# voltage_conditioning.net
KiCad netlist of a schematic drawn in Altium Designer
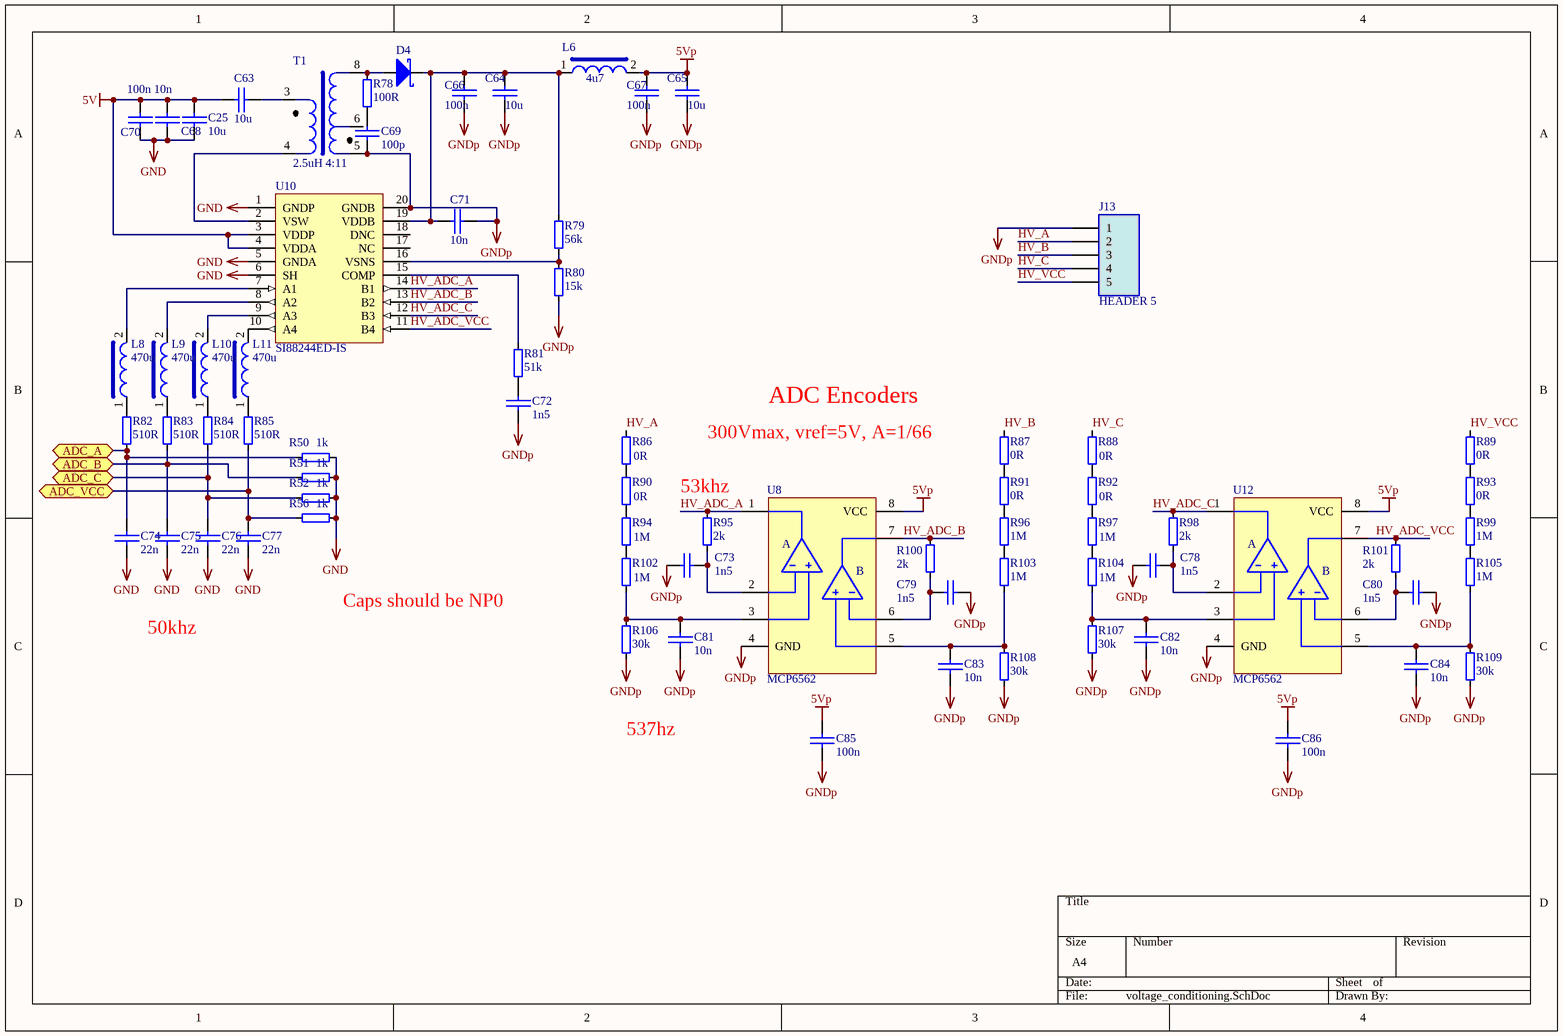
[diagram p0: voltage_conditioning.SchDoc]

(export (version "E")
  (design (tool "Eeschema 10.0.6"))
  (components
    (comp (ref "C25")
      (value "10u")
      (footprint "0805")
      (description "Capacitor")
      (libsource (lib "Schematic Library") (part "CAPACITOR"))
    )
    (comp (ref "C63")
      (value "10u")
      (footprint "0805")
      (description "Capacitor")
      (libsource (lib "Schematic Library") (part "CAPACITOR"))
    )
    (comp (ref "C64")
      (value "10u")
      (footprint "0805")
      (description "Capacitor")
      (libsource (lib "Schematic Library") (part "CAPACITOR"))
    )
    (comp (ref "C65")
      (value "10u")
      (footprint "0805")
      (description "Capacitor")
      (libsource (lib "Schematic Library") (part "CAPACITOR"))
    )
    (comp (ref "C66")
      (value "100n")
      (footprint "0603")
      (description "Capacitor")
      (libsource (lib "Schematic Library") (part "CAPACITOR"))
    )
    (comp (ref "C67")
      (value "100n")
      (footprint "0603")
      (description "Capacitor")
      (libsource (lib "Schematic Library") (part "CAPACITOR"))
    )
    (comp (ref "C68")
      (value "10n")
      (footprint "0603")
      (description "Capacitor")
      (libsource (lib "Schematic Library") (part "CAPACITOR"))
    )
    (comp (ref "C69")
      (value "100p")
      (footprint "0603")
      (fields (field (name "DIGIKEY PART NUMBER") "PCC2153CT-ND"))
      (libsource (lib "*") (part "CAP"))
    )
    (comp (ref "C70")
      (value "100n")
      (footprint "0603")
      (description "Capacitor")
      (libsource (lib "Schematic Library") (part "CAPACITOR"))
    )
    (comp (ref "C71")
      (value "10n")
      (footprint "0603")
      (description "Capacitor")
      (libsource (lib "Schematic Library") (part "CAPACITOR"))
    )
    (comp (ref "C72")
      (value "1n5")
      (footprint "0603")
      (fields (field (name "DIGIKEY PART NUMBER") "PCC2153CT-ND"))
      (libsource (lib "*") (part "CAP"))
    )
    (comp (ref "C73")
      (value "1n5")
      (footprint "0603")
      (description "COG/NPO")
      (libsource (lib "Schematic Library") (part "CAPACITOR"))
    )
    (comp (ref "C74")
      (value "22n")
      (footprint "0603")
      (description "Capacitor")
      (libsource (lib "Schematic Library") (part "CAPACITOR"))
    )
    (comp (ref "C75")
      (value "22n")
      (footprint "0603")
      (description "Capacitor")
      (libsource (lib "Schematic Library") (part "CAPACITOR"))
    )
    (comp (ref "C76")
      (value "22n")
      (footprint "0603")
      (description "Capacitor")
      (libsource (lib "Schematic Library") (part "CAPACITOR"))
    )
    (comp (ref "C77")
      (value "22n")
      (footprint "0603")
      (description "Capacitor")
      (libsource (lib "Schematic Library") (part "CAPACITOR"))
    )
    (comp (ref "C78")
      (value "1n5")
      (footprint "0603")
      (description "COG/NPO")
      (libsource (lib "Schematic Library") (part "CAPACITOR"))
    )
    (comp (ref "C79")
      (value "1n5")
      (footprint "0603")
      (description "Capacitor")
      (libsource (lib "Schematic Library") (part "CAPACITOR"))
    )
    (comp (ref "C80")
      (value "1n5")
      (footprint "0603")
      (description "Capacitor")
      (libsource (lib "Schematic Library") (part "CAPACITOR"))
    )
    (comp (ref "C81")
      (value "10n")
      (footprint "0603")
      (description "Capacitor")
      (libsource (lib "Schematic Library") (part "CAPACITOR"))
    )
    (comp (ref "C82")
      (value "10n")
      (footprint "0603")
      (description "Capacitor")
      (libsource (lib "Schematic Library") (part "CAPACITOR"))
    )
    (comp (ref "C83")
      (value "10n")
      (footprint "0603")
      (description "Capacitor")
      (libsource (lib "Schematic Library") (part "CAPACITOR"))
    )
    (comp (ref "C84")
      (value "10n")
      (footprint "0603")
      (description "Capacitor")
      (libsource (lib "Schematic Library") (part "CAPACITOR"))
    )
    (comp (ref "C85") (value "100n") (footprint "0603") (libsource (lib "*") (part "CAP")))
    (comp (ref "C86") (value "100n") (footprint "0603") (libsource (lib "*") (part "CAP")))
    (comp (ref "D4")
      (value "DIODE SCHOTTKY")
      (footprint "SOD323-AK")
      (description "Schottky Diode")
      (libsource (lib "Schematic Library") (part "DIODE SCHOTTKY"))
    )
    (comp (ref "J13")
      (value "HEADER 5")
      (footprint "HDR5-5mm")
      (description "4 Pin Header")
      (libsource (lib "Schematic Library") (part "HEADER 5"))
    )
    (comp (ref "L6")
      (value "4u7")
      (footprint "0805")
      (description "Standard single coil inductor")
      (fields (field (name "DIGIKEY PART NUMBER") "587-2907-1-ND"))
      (libsource (lib "Schematic Library") (part "INDUCTOR-1 COIL"))
    )
    (comp (ref "L8")
      (value "470u")
      (footprint "0805")
      (description "Standard single coil inductor")
      (libsource (lib "Schematic Library") (part "INDUCTOR-1 COIL"))
    )
    (comp (ref "L9")
      (value "470u")
      (footprint "0805")
      (description "Standard single coil inductor")
      (libsource (lib "Schematic Library") (part "INDUCTOR-1 COIL"))
    )
    (comp (ref "L10")
      (value "470u")
      (footprint "0805")
      (description "Standard single coil inductor")
      (libsource (lib "Schematic Library") (part "INDUCTOR-1 COIL"))
    )
    (comp (ref "L11")
      (value "470u")
      (footprint "0805")
      (description "Standard single coil inductor")
      (libsource (lib "Schematic Library") (part "INDUCTOR-1 COIL"))
    )
    (comp (ref "R50")
      (value "1k")
      (footprint "0603")
      (description "Resistor")
      (libsource (lib "Schematic Library") (part "RESISTOR"))
    )
    (comp (ref "R51")
      (value "1k")
      (footprint "0603")
      (description "Resistor")
      (libsource (lib "Schematic Library") (part "RESISTOR"))
    )
    (comp (ref "R52")
      (value "1k")
      (footprint "0603")
      (description "Resistor")
      (libsource (lib "Schematic Library") (part "RESISTOR"))
    )
    (comp (ref "R56")
      (value "1k")
      (footprint "0603")
      (description "Resistor")
      (libsource (lib "Schematic Library") (part "RESISTOR"))
    )
    (comp (ref "R78")
      (value "100R")
      (footprint "0603")
      (description "Resistor")
      (libsource (lib "Schematic Library") (part "RESISTOR"))
    )
    (comp (ref "R79")
      (value "56k")
      (footprint "0603")
      (description "Resistor")
      (libsource (lib "Schematic Library") (part "RESISTOR"))
    )
    (comp (ref "R80")
      (value "15k")
      (footprint "0603")
      (description "Resistor")
      (libsource (lib "Schematic Library") (part "RESISTOR"))
    )
    (comp (ref "R81")
      (value "51k")
      (footprint "0603")
      (description "Resistor")
      (libsource (lib "Schematic Library") (part "RESISTOR"))
    )
    (comp (ref "R82")
      (value "510R")
      (footprint "0603")
      (description "Resistor")
      (libsource (lib "Schematic Library") (part "RESISTOR"))
    )
    (comp (ref "R83")
      (value "510R")
      (footprint "0603")
      (description "Resistor")
      (libsource (lib "Schematic Library") (part "RESISTOR"))
    )
    (comp (ref "R84")
      (value "510R")
      (footprint "0603")
      (description "Resistor")
      (libsource (lib "Schematic Library") (part "RESISTOR"))
    )
    (comp (ref "R85")
      (value "510R")
      (footprint "0603")
      (description "Resistor")
      (libsource (lib "Schematic Library") (part "RESISTOR"))
    )
    (comp (ref "R86")
      (value "0R")
      (footprint "1206")
      (description "Resistor")
      (libsource (lib "Schematic Library") (part "RESISTOR"))
    )
    (comp (ref "R87")
      (value "0R")
      (footprint "1206")
      (description "Resistor")
      (libsource (lib "Schematic Library") (part "RESISTOR"))
    )
    (comp (ref "R88")
      (value "0R")
      (footprint "1206")
      (description "Resistor")
      (libsource (lib "Schematic Library") (part "RESISTOR"))
    )
    (comp (ref "R89")
      (value "0R")
      (footprint "1206")
      (description "Resistor")
      (libsource (lib "Schematic Library") (part "RESISTOR"))
    )
    (comp (ref "R90")
      (value "0R")
      (footprint "1206")
      (description "Resistor")
      (libsource (lib "Schematic Library") (part "RESISTOR"))
    )
    (comp (ref "R91")
      (value "0R")
      (footprint "1206")
      (description "Resistor")
      (libsource (lib "Schematic Library") (part "RESISTOR"))
    )
    (comp (ref "R92")
      (value "0R")
      (footprint "1206")
      (description "Resistor")
      (libsource (lib "Schematic Library") (part "RESISTOR"))
    )
    (comp (ref "R93")
      (value "0R")
      (footprint "1206")
      (description "Resistor")
      (libsource (lib "Schematic Library") (part "RESISTOR"))
    )
    (comp (ref "R94")
      (value "1M")
      (footprint "1206")
      (description "Resistor")
      (libsource (lib "Schematic Library") (part "RESISTOR"))
    )
    (comp (ref "R95")
      (value "2k")
      (footprint "0603")
      (description "Resistor")
      (libsource (lib "Schematic Library") (part "RESISTOR"))
    )
    (comp (ref "R96")
      (value "1M")
      (footprint "1206")
      (description "Resistor")
      (libsource (lib "Schematic Library") (part "RESISTOR"))
    )
    (comp (ref "R97")
      (value "1M")
      (footprint "1206")
      (description "Resistor")
      (libsource (lib "Schematic Library") (part "RESISTOR"))
    )
    (comp (ref "R98")
      (value "2k")
      (footprint "0603")
      (description "Resistor")
      (libsource (lib "Schematic Library") (part "RESISTOR"))
    )
    (comp (ref "R99")
      (value "1M")
      (footprint "1206")
      (description "Resistor")
      (libsource (lib "Schematic Library") (part "RESISTOR"))
    )
    (comp (ref "R100")
      (value "2k")
      (footprint "0603")
      (description "Resistor")
      (libsource (lib "Schematic Library") (part "RESISTOR"))
    )
    (comp (ref "R101")
      (value "2k")
      (footprint "0603")
      (description "Resistor")
      (libsource (lib "Schematic Library") (part "RESISTOR"))
    )
    (comp (ref "R102")
      (value "1M")
      (footprint "1206")
      (description "Resistor")
      (libsource (lib "Schematic Library") (part "RESISTOR"))
    )
    (comp (ref "R103")
      (value "1M")
      (footprint "1206")
      (description "Resistor")
      (libsource (lib "Schematic Library") (part "RESISTOR"))
    )
    (comp (ref "R104")
      (value "1M")
      (footprint "1206")
      (description "Resistor")
      (libsource (lib "Schematic Library") (part "RESISTOR"))
    )
    (comp (ref "R105")
      (value "1M")
      (footprint "1206")
      (description "Resistor")
      (libsource (lib "Schematic Library") (part "RESISTOR"))
    )
    (comp (ref "R106")
      (value "30k")
      (footprint "0603")
      (description "Resistor")
      (libsource (lib "Schematic Library") (part "RESISTOR"))
    )
    (comp (ref "R107")
      (value "30k")
      (footprint "0603")
      (description "Resistor")
      (libsource (lib "Schematic Library") (part "RESISTOR"))
    )
    (comp (ref "R108")
      (value "30k")
      (footprint "0603")
      (description "Resistor")
      (libsource (lib "Schematic Library") (part "RESISTOR"))
    )
    (comp (ref "R109")
      (value "30k")
      (footprint "0603")
      (description "Resistor")
      (libsource (lib "Schematic Library") (part "RESISTOR"))
    )
    (comp (ref "T1")
      (value "2.5uH 4:11")
      (footprint "RM5/I")
      (description "2Coil Transformer 1 on left 1 on right with tap")
      (libsource (lib "LBC") (part "TRANSFORMER-2 COIL 1L 1R_1t"))
    )
    (comp (ref "U8")
      (value "MCP6562")
      (footprint "MSOP8")
      (libsource (lib "Schematic Library") (part "COMPARATOR DUAL draft"))
    )
    (comp (ref "U10")
      (value "SI88244ED-IS")
      (footprint "SLAB-SOIC-20-WB_N")
      (fields (field (name "MANUFACTURER") "Silicon Labs") (field (name "PARTNUMBER") "SI88243ED-IS"))
      (libsource (lib "LBC") (part "SI88243ED-IS"))
    )
    (comp (ref "U12")
      (value "MCP6562")
      (footprint "MSOP8")
      (libsource (lib "Schematic Library") (part "COMPARATOR DUAL draft"))
    )
  )
  (nets
    (net (code "1") (name "/ADC_A") (class "Default")
      (node (ref "C74") (pin "2") (pinfunction "2_2") (pintype "passive"))
      (node (ref "R50") (pin "2") (pintype "passive"))
      (node (ref "R82") (pin "1") (pintype "passive"))
    )
    (net (code "2") (name "/ADC_B") (class "Default")
      (node (ref "C75") (pin "2") (pinfunction "2_2") (pintype "passive"))
      (node (ref "R51") (pin "2") (pintype "passive"))
      (node (ref "R83") (pin "1") (pintype "passive"))
    )
    (net (code "3") (name "/ADC_C") (class "Default")
      (node (ref "C76") (pin "2") (pinfunction "2_2") (pintype "passive"))
      (node (ref "R52") (pin "2") (pintype "passive"))
      (node (ref "R84") (pin "1") (pintype "passive"))
    )
    (net (code "4") (name "/ADC_VCC") (class "Default")
      (node (ref "C77") (pin "2") (pinfunction "2_2") (pintype "passive"))
      (node (ref "R56") (pin "2") (pintype "passive"))
      (node (ref "R85") (pin "1") (pintype "passive"))
    )
    (net (code "5") (name "/HV_A") (class "Default")
      (node (ref "J13") (pin "2") (pinfunction "2_2") (pintype "passive"))
      (node (ref "R86") (pin "2") (pintype "passive"))
    )
    (net (code "6") (name "/HV_ADC_A") (class "Default")
      (node (ref "R95") (pin "2") (pintype "passive"))
      (node (ref "U10") (pin "14") (pinfunction "B1_14") (pintype "output"))
      (node (ref "U8") (pin "1") (pinfunction "OUTA_1") (pintype "passive"))
    )
    (net (code "7") (name "/HV_ADC_B") (class "Default")
      (node (ref "R100") (pin "2") (pintype "passive"))
      (node (ref "U10") (pin "13") (pinfunction "B2_13") (pintype "input"))
      (node (ref "U8") (pin "7") (pinfunction "OUTB_7") (pintype "passive"))
    )
    (net (code "8") (name "/HV_ADC_C") (class "Default")
      (node (ref "R98") (pin "2") (pintype "passive"))
      (node (ref "U10") (pin "12") (pinfunction "B3_12") (pintype "input"))
      (node (ref "U12") (pin "1") (pinfunction "OUTA_1") (pintype "passive"))
    )
    (net (code "9") (name "/HV_ADC_VCC") (class "Default")
      (node (ref "R101") (pin "2") (pintype "passive"))
      (node (ref "U10") (pin "11") (pinfunction "B4_11") (pintype "input"))
      (node (ref "U12") (pin "7") (pinfunction "OUTB_7") (pintype "passive"))
    )
    (net (code "10") (name "/HV_B") (class "Default")
      (node (ref "J13") (pin "3") (pinfunction "3_3") (pintype "passive"))
      (node (ref "R87") (pin "2") (pintype "passive"))
    )
    (net (code "11") (name "/HV_C") (class "Default")
      (node (ref "J13") (pin "4") (pinfunction "4_4") (pintype "passive"))
      (node (ref "R88") (pin "2") (pintype "passive"))
    )
    (net (code "12") (name "/HV_VCC") (class "Default")
      (node (ref "J13") (pin "5") (pinfunction "5_5") (pintype "passive"))
      (node (ref "R89") (pin "2") (pintype "passive"))
    )
    (net (code "13") (name "5V") (class "Default")
      (node (ref "C25") (pin "2") (pinfunction "2_2") (pintype "passive"))
      (node (ref "C63") (pin "1") (pinfunction "1_1") (pintype "passive"))
      (node (ref "C68") (pin "1") (pinfunction "1_1") (pintype "passive"))
      (node (ref "C70") (pin "1") (pinfunction "1_1") (pintype "passive"))
      (node (ref "U10") (pin "3") (pinfunction "VDDP_3") (pintype "passive"))
      (node (ref "U10") (pin "4") (pinfunction "VDDA_4") (pintype "passive"))
    )
    (net (code "14") (name "5Vp") (class "Default")
      (node (ref "C65") (pin "1") (pinfunction "1_1") (pintype "passive"))
      (node (ref "C67") (pin "1") (pinfunction "1_1") (pintype "passive"))
      (node (ref "C85") (pin "1") (pinfunction "1_1") (pintype "passive"))
      (node (ref "C86") (pin "1") (pinfunction "1_1") (pintype "passive"))
      (node (ref "L6") (pin "2") (pinfunction "2_2") (pintype "passive"))
      (node (ref "U12") (pin "8") (pinfunction "VCC_8") (pintype "passive"))
      (node (ref "U8") (pin "8") (pinfunction "VCC_8") (pintype "passive"))
    )
    (net (code "15") (name "GND") (class "Default")
      (node (ref "C25") (pin "1") (pinfunction "1_1") (pintype "passive"))
      (node (ref "C68") (pin "2") (pinfunction "2_2") (pintype "passive"))
      (node (ref "C70") (pin "2") (pinfunction "2_2") (pintype "passive"))
      (node (ref "C74") (pin "1") (pinfunction "1_1") (pintype "passive"))
      (node (ref "C75") (pin "1") (pinfunction "1_1") (pintype "passive"))
      (node (ref "C76") (pin "1") (pinfunction "1_1") (pintype "passive"))
      (node (ref "C77") (pin "1") (pinfunction "1_1") (pintype "passive"))
      (node (ref "R50") (pin "1") (pintype "passive"))
      (node (ref "R51") (pin "1") (pintype "passive"))
      (node (ref "R52") (pin "1") (pintype "passive"))
      (node (ref "R56") (pin "1") (pintype "passive"))
      (node (ref "U10") (pin "1") (pinfunction "GNDP_1") (pintype "passive"))
      (node (ref "U10") (pin "5") (pinfunction "GNDA_5") (pintype "passive"))
      (node (ref "U10") (pin "6") (pinfunction "SH_6") (pintype "passive"))
    )
    (net (code "16") (name "GNDp") (class "Default")
      (node (ref "C64") (pin "2") (pinfunction "2_2") (pintype "passive"))
      (node (ref "C65") (pin "2") (pinfunction "2_2") (pintype "passive"))
      (node (ref "C66") (pin "2") (pinfunction "2_2") (pintype "passive"))
      (node (ref "C67") (pin "2") (pinfunction "2_2") (pintype "passive"))
      (node (ref "C69") (pin "2") (pinfunction "2_2") (pintype "passive"))
      (node (ref "C71") (pin "2") (pinfunction "2_2") (pintype "passive"))
      (node (ref "C72") (pin "2") (pinfunction "2_2") (pintype "passive"))
      (node (ref "C73") (pin "1") (pinfunction "1_1") (pintype "passive"))
      (node (ref "C78") (pin "1") (pinfunction "1_1") (pintype "passive"))
      (node (ref "C79") (pin "1") (pinfunction "1_1") (pintype "passive"))
      (node (ref "C80") (pin "1") (pinfunction "1_1") (pintype "passive"))
      (node (ref "C81") (pin "1") (pinfunction "1_1") (pintype "passive"))
      (node (ref "C82") (pin "1") (pinfunction "1_1") (pintype "passive"))
      (node (ref "C83") (pin "2") (pinfunction "2_2") (pintype "passive"))
      (node (ref "C84") (pin "2") (pinfunction "2_2") (pintype "passive"))
      (node (ref "C85") (pin "2") (pinfunction "2_2") (pintype "passive"))
      (node (ref "C86") (pin "2") (pinfunction "2_2") (pintype "passive"))
      (node (ref "J13") (pin "1") (pinfunction "1_1") (pintype "passive"))
      (node (ref "R106") (pin "1") (pintype "passive"))
      (node (ref "R107") (pin "1") (pintype "passive"))
      (node (ref "R108") (pin "2") (pintype "passive"))
      (node (ref "R109") (pin "2") (pintype "passive"))
      (node (ref "R80") (pin "2") (pintype "passive"))
      (node (ref "T1") (pin "5") (pinfunction "5_5") (pintype "passive"))
      (node (ref "U10") (pin "20") (pinfunction "GNDB_20") (pintype "passive"))
      (node (ref "U12") (pin "4") (pinfunction "GND_4") (pintype "passive"))
      (node (ref "U8") (pin "4") (pinfunction "GND_4") (pintype "passive"))
    )
    (net (code "17") (name "Net-(C63-Pad2)") (class "Default")
      (node (ref "C63") (pin "2") (pinfunction "2_2") (pintype "passive"))
      (node (ref "T1") (pin "3") (pinfunction "3_3") (pintype "passive"))
    )
    (net (code "18") (name "Net-(C69-Pad1)") (class "Default")
      (node (ref "C69") (pin "1") (pinfunction "1_1") (pintype "passive"))
      (node (ref "R78") (pin "1") (pintype "passive"))
    )
    (net (code "19") (name "Net-(C72-Pad1)") (class "Default")
      (node (ref "C72") (pin "1") (pinfunction "1_1") (pintype "passive"))
      (node (ref "R81") (pin "1") (pintype "passive"))
    )
    (net (code "20") (name "Net-(D4-PadA)") (class "Default")
      (node (ref "D4") (pin "A") (pinfunction "A_A") (pintype "passive"))
      (node (ref "R78") (pin "2") (pintype "passive"))
      (node (ref "T1") (pin "8") (pinfunction "8_8") (pintype "passive"))
    )
    (net (code "21") (name "Net-(L8-Pad1)") (class "Default")
      (node (ref "L8") (pin "1") (pinfunction "1_1") (pintype "passive"))
      (node (ref "R82") (pin "2") (pintype "passive"))
    )
    (net (code "22") (name "Net-(L9-Pad1)") (class "Default")
      (node (ref "L9") (pin "1") (pinfunction "1_1") (pintype "passive"))
      (node (ref "R83") (pin "2") (pintype "passive"))
    )
    (net (code "23") (name "Net-(L10-Pad1)") (class "Default")
      (node (ref "L10") (pin "1") (pinfunction "1_1") (pintype "passive"))
      (node (ref "R84") (pin "2") (pintype "passive"))
    )
    (net (code "24") (name "Net-(L11-Pad1)") (class "Default")
      (node (ref "L11") (pin "1") (pinfunction "1_1") (pintype "passive"))
      (node (ref "R85") (pin "2") (pintype "passive"))
    )
    (net (code "25") (name "Net-(R86-Pad1)") (class "Default")
      (node (ref "R86") (pin "1") (pintype "passive"))
      (node (ref "R90") (pin "2") (pintype "passive"))
    )
    (net (code "26") (name "Net-(R87-Pad1)") (class "Default")
      (node (ref "R87") (pin "1") (pintype "passive"))
      (node (ref "R91") (pin "2") (pintype "passive"))
    )
    (net (code "27") (name "Net-(R88-Pad1)") (class "Default")
      (node (ref "R88") (pin "1") (pintype "passive"))
      (node (ref "R92") (pin "2") (pintype "passive"))
    )
    (net (code "28") (name "Net-(R89-Pad1)") (class "Default")
      (node (ref "R89") (pin "1") (pintype "passive"))
      (node (ref "R93") (pin "2") (pintype "passive"))
    )
    (net (code "29") (name "Net-(R90-Pad1)") (class "Default")
      (node (ref "R90") (pin "1") (pintype "passive"))
      (node (ref "R94") (pin "2") (pintype "passive"))
    )
    (net (code "30") (name "Net-(R91-Pad1)") (class "Default")
      (node (ref "R91") (pin "1") (pintype "passive"))
      (node (ref "R96") (pin "2") (pintype "passive"))
    )
    (net (code "31") (name "Net-(R92-Pad1)") (class "Default")
      (node (ref "R92") (pin "1") (pintype "passive"))
      (node (ref "R97") (pin "2") (pintype "passive"))
    )
    (net (code "32") (name "Net-(R93-Pad1)") (class "Default")
      (node (ref "R93") (pin "1") (pintype "passive"))
      (node (ref "R99") (pin "2") (pintype "passive"))
    )
    (net (code "33") (name "Net-(R102-Pad2)") (class "Default")
      (node (ref "R102") (pin "2") (pintype "passive"))
      (node (ref "R94") (pin "1") (pintype "passive"))
    )
    (net (code "34") (name "Net-(R103-Pad2)") (class "Default")
      (node (ref "R103") (pin "2") (pintype "passive"))
      (node (ref "R96") (pin "1") (pintype "passive"))
    )
    (net (code "35") (name "Net-(R104-Pad2)") (class "Default")
      (node (ref "R104") (pin "2") (pintype "passive"))
      (node (ref "R97") (pin "1") (pintype "passive"))
    )
    (net (code "36") (name "Net-(R105-Pad2)") (class "Default")
      (node (ref "R105") (pin "2") (pintype "passive"))
      (node (ref "R99") (pin "1") (pintype "passive"))
    )
    (net (code "37") (name "Net-(U8-+A)") (class "Default")
      (node (ref "C81") (pin "2") (pinfunction "2_2") (pintype "passive"))
      (node (ref "R102") (pin "1") (pintype "passive"))
      (node (ref "R106") (pin "2") (pintype "passive"))
      (node (ref "U8") (pin "3") (pinfunction "+A_3") (pintype "passive"))
    )
    (net (code "38") (name "Net-(U8-+B)") (class "Default")
      (node (ref "C83") (pin "1") (pinfunction "1_1") (pintype "passive"))
      (node (ref "R103") (pin "1") (pintype "passive"))
      (node (ref "R108") (pin "1") (pintype "passive"))
      (node (ref "U8") (pin "5") (pinfunction "+B_5") (pintype "passive"))
    )
    (net (code "39") (name "Net-(U8--A)") (class "Default")
      (node (ref "C73") (pin "2") (pinfunction "2_2") (pintype "passive"))
      (node (ref "R95") (pin "1") (pintype "passive"))
      (node (ref "U8") (pin "2") (pinfunction "-A_2") (pintype "passive"))
    )
    (net (code "40") (name "Net-(U8--B)") (class "Default")
      (node (ref "C79") (pin "2") (pinfunction "2_2") (pintype "passive"))
      (node (ref "R100") (pin "1") (pintype "passive"))
      (node (ref "U8") (pin "6") (pinfunction "-B_6") (pintype "passive"))
    )
    (net (code "41") (name "Net-(U10-A1)") (class "Default")
      (node (ref "L8") (pin "2") (pinfunction "2_2") (pintype "passive"))
      (node (ref "U10") (pin "7") (pinfunction "A1_7") (pintype "input"))
    )
    (net (code "42") (name "Net-(U10-A2)") (class "Default")
      (node (ref "L9") (pin "2") (pinfunction "2_2") (pintype "passive"))
      (node (ref "U10") (pin "8") (pinfunction "A2_8") (pintype "output"))
    )
    (net (code "43") (name "Net-(U10-A3)") (class "Default")
      (node (ref "L10") (pin "2") (pinfunction "2_2") (pintype "passive"))
      (node (ref "U10") (pin "9") (pinfunction "A3_9") (pintype "output"))
    )
    (net (code "44") (name "Net-(U10-A4)") (class "Default")
      (node (ref "L11") (pin "2") (pinfunction "2_2") (pintype "passive"))
      (node (ref "U10") (pin "10") (pinfunction "A4_10") (pintype "output"))
    )
    (net (code "45") (name "Net-(U10-COMP)") (class "Default")
      (node (ref "R81") (pin "2") (pintype "passive"))
      (node (ref "U10") (pin "15") (pinfunction "COMP_15") (pintype "passive"))
    )
    (net (code "46") (name "Net-(U10-VDDB)") (class "Default")
      (node (ref "C64") (pin "1") (pinfunction "1_1") (pintype "passive"))
      (node (ref "C66") (pin "1") (pinfunction "1_1") (pintype "passive"))
      (node (ref "C71") (pin "1") (pinfunction "1_1") (pintype "passive"))
      (node (ref "D4") (pin "K") (pinfunction "K_K") (pintype "passive"))
      (node (ref "L6") (pin "1") (pinfunction "1_1") (pintype "passive"))
      (node (ref "R79") (pin "2") (pintype "passive"))
      (node (ref "U10") (pin "19") (pinfunction "VDDB_19") (pintype "passive"))
    )
    (net (code "47") (name "Net-(U10-VSNS)") (class "Default")
      (node (ref "R79") (pin "1") (pintype "passive"))
      (node (ref "R80") (pin "1") (pintype "passive"))
      (node (ref "U10") (pin "16") (pinfunction "VSNS_16") (pintype "passive"))
    )
    (net (code "48") (name "Net-(U10-VSW)") (class "Default")
      (node (ref "T1") (pin "4") (pinfunction "4_4") (pintype "passive"))
      (node (ref "U10") (pin "2") (pinfunction "VSW_2") (pintype "passive"))
    )
    (net (code "49") (name "Net-(U12-+A)") (class "Default")
      (node (ref "C82") (pin "2") (pinfunction "2_2") (pintype "passive"))
      (node (ref "R104") (pin "1") (pintype "passive"))
      (node (ref "R107") (pin "2") (pintype "passive"))
      (node (ref "U12") (pin "3") (pinfunction "+A_3") (pintype "passive"))
    )
    (net (code "50") (name "Net-(U12-+B)") (class "Default")
      (node (ref "C84") (pin "1") (pinfunction "1_1") (pintype "passive"))
      (node (ref "R105") (pin "1") (pintype "passive"))
      (node (ref "R109") (pin "1") (pintype "passive"))
      (node (ref "U12") (pin "5") (pinfunction "+B_5") (pintype "passive"))
    )
    (net (code "51") (name "Net-(U12--A)") (class "Default")
      (node (ref "C78") (pin "2") (pinfunction "2_2") (pintype "passive"))
      (node (ref "R98") (pin "1") (pintype "passive"))
      (node (ref "U12") (pin "2") (pinfunction "-A_2") (pintype "passive"))
    )
    (net (code "52") (name "Net-(U12--B)") (class "Default")
      (node (ref "C80") (pin "2") (pinfunction "2_2") (pintype "passive"))
      (node (ref "R101") (pin "1") (pintype "passive"))
      (node (ref "U12") (pin "6") (pinfunction "-B_6") (pintype "passive"))
    )
    (net (code "53") (name "unconnected-(T1-Pad6)") (class "Default")
      (node (ref "T1") (pin "6") (pinfunction "6_6") (pintype "passive"))
    )
    (net (code "54") (name "unconnected-(U10-DNC-Pad18)") (class "Default")
      (node (ref "U10") (pin "18") (pinfunction "DNC_18") (pintype "passive"))
    )
    (net (code "55") (name "unconnected-(U10-NC-Pad17)") (class "Default")
      (node (ref "U10") (pin "17") (pinfunction "NC_17") (pintype "passive"))
    )
  )
)
